# gps_and_sensor_20171211.net
KiCad netlist of a schematic drawn in EAGLE
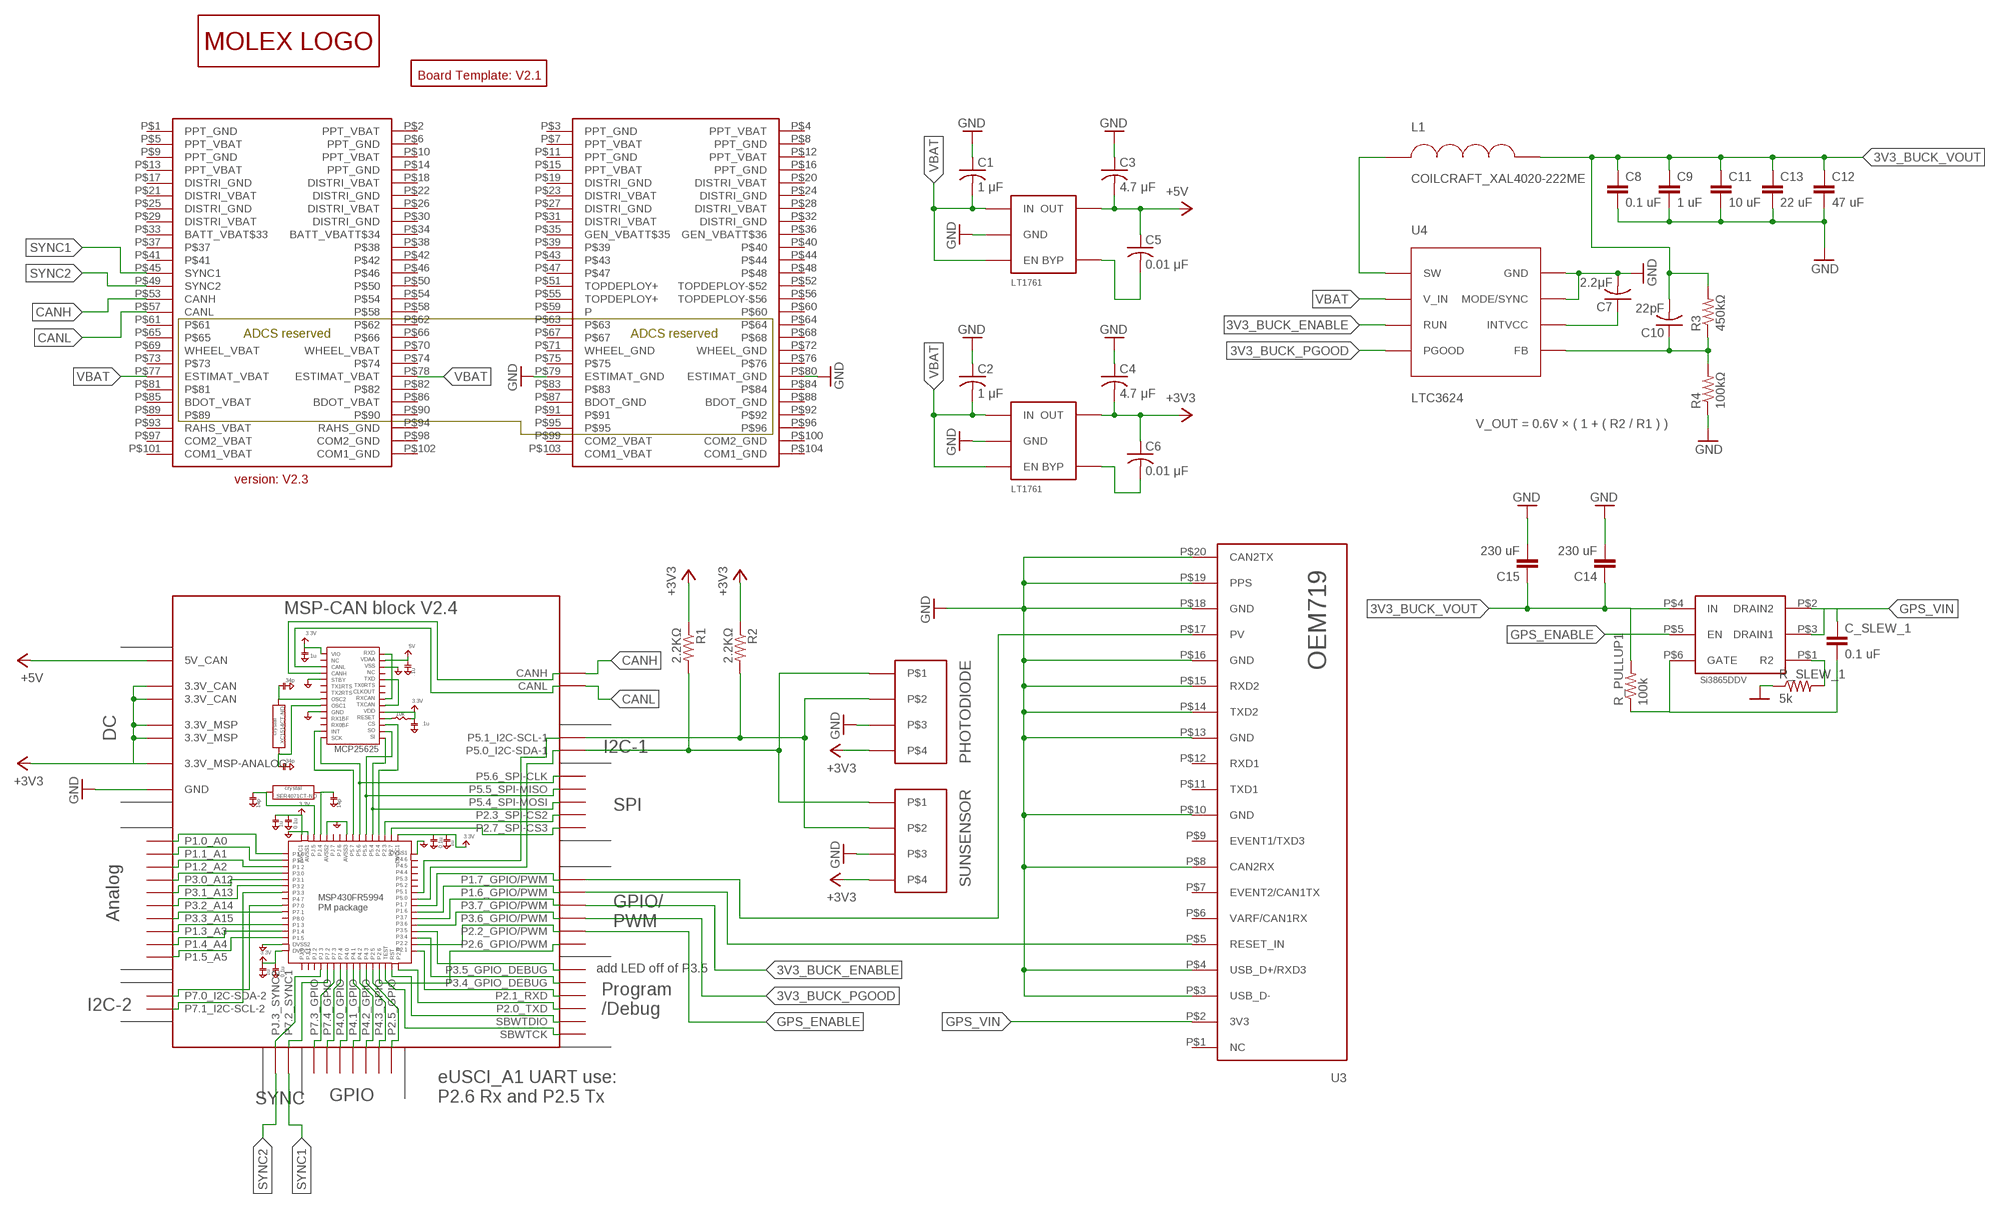
[diagram p0: schematic, sheet 1]

(export (version "E")
  (design (tool "Eeschema 10.0.6"))
  (components
    (comp (ref "B1")
      (value "BOARD_TEMPLATE1")
      (footprint "eagle-import:BOARD_TEMPLATE")
      (libsource (lib "eagle-import") (part "BOARD_TEMPLATE1"))
    )
    (comp (ref "BLK1")
      (value "MSP-CAN_BLOCK")
      (footprint "eagle-import:MSP-CAN_BLOCK")
      (libsource (lib "eagle-import") (part "MSP-CAN_BLOCK"))
    )
    (comp (ref "C1")
      (value "1 μF")
      (footprint "eagle-import:C0805")
      (libsource (lib "eagle-import") (part "C-USC0805"))
    )
    (comp (ref "C2")
      (value "1 μF")
      (footprint "eagle-import:C0805")
      (libsource (lib "eagle-import") (part "C-USC0805"))
    )
    (comp (ref "C3")
      (value "4.7 μF")
      (footprint "eagle-import:C0805")
      (libsource (lib "eagle-import") (part "C-USC0805"))
    )
    (comp (ref "C4")
      (value "4.7 μF")
      (footprint "eagle-import:C0805")
      (libsource (lib "eagle-import") (part "C-USC0805"))
    )
    (comp (ref "C5")
      (value "0.01 μF")
      (footprint "eagle-import:C0805")
      (libsource (lib "eagle-import") (part "C-USC0805"))
    )
    (comp (ref "C6")
      (value "0.01 μF")
      (footprint "eagle-import:C0805")
      (libsource (lib "eagle-import") (part "C-USC0805"))
    )
    (comp (ref "C7")
      (value "2.2μF")
      (footprint "eagle-import:C0805")
      (libsource (lib "eagle-import") (part "C-USC0805"))
    )
    (comp (ref "C8")
      (value "0.1 uF")
      (footprint "eagle-import:0805")
      (libsource (lib "eagle-import") (part "CAPACITOR0805"))
    )
    (comp (ref "C9")
      (value "1 uF")
      (footprint "eagle-import:0805")
      (libsource (lib "eagle-import") (part "CAPACITOR0805"))
    )
    (comp (ref "C10")
      (value "22pF")
      (footprint "eagle-import:C0805")
      (libsource (lib "eagle-import") (part "C-USC0805"))
    )
    (comp (ref "C11")
      (value "10 uF")
      (footprint "eagle-import:0805")
      (libsource (lib "eagle-import") (part "CAPACITOR0805"))
    )
    (comp (ref "C12")
      (value "47 uF")
      (footprint "eagle-import:1206")
      (libsource (lib "eagle-import") (part "CAPACITOR1206"))
    )
    (comp (ref "C13")
      (value "22 uF")
      (footprint "eagle-import:1206")
      (libsource (lib "eagle-import") (part "CAPACITOR1206"))
    )
    (comp (ref "C14")
      (value "230 uF")
      (footprint "eagle-import:PANASONIC_SVPG")
      (libsource (lib "eagle-import") (part "CAPACITORPANASONIC_16SVPG270M"))
    )
    (comp (ref "C15")
      (value "230 uF")
      (footprint "eagle-import:PANASONIC_SVPG")
      (libsource (lib "eagle-import") (part "CAPACITORPANASONIC_16SVPG270M"))
    )
    (comp (ref "CONN1")
      (value "PC104_CONNECTOR")
      (footprint "eagle-import:PC104_CONNECTOR")
      (libsource (lib "eagle-import") (part "PC104_CONNECTOR"))
    )
    (comp (ref "C_SLEW_1")
      (value "0.1 uF")
      (footprint "eagle-import:0805")
      (libsource (lib "eagle-import") (part "CAPACITOR0805"))
    )
    (comp (ref "L1")
      (value "COILCRAFT_XAL4020-222ME")
      (footprint "eagle-import:COILCRAFT_XAL4020")
      (libsource (lib "eagle-import") (part "COILCRAFT_XAL4020-222ME"))
    )
    (comp (ref "PHOTODIODE")
      (value "PICOLOCK_4")
      (footprint "eagle-import:PICOLOCK_4")
      (libsource (lib "eagle-import") (part "PICOLOCK_4"))
    )
    (comp (ref "R1")
      (value "2.2KΩ")
      (footprint "eagle-import:R0805")
      (libsource (lib "eagle-import") (part "R-US_R0805"))
    )
    (comp (ref "R2")
      (value "2.2KΩ")
      (footprint "eagle-import:R0805")
      (libsource (lib "eagle-import") (part "R-US_R0805"))
    )
    (comp (ref "R3")
      (value "450kΩ")
      (footprint "eagle-import:R0805")
      (libsource (lib "eagle-import") (part "R-US_R0805"))
    )
    (comp (ref "R4")
      (value "100kΩ")
      (footprint "eagle-import:R0805")
      (libsource (lib "eagle-import") (part "R-US_R0805"))
    )
    (comp (ref "R_PULLUP1")
      (value "100k")
      (footprint "eagle-import:0805")
      (libsource (lib "eagle-import") (part "RESISTOR0805"))
    )
    (comp (ref "R_SLEW_1")
      (value "5k")
      (footprint "eagle-import:0805")
      (libsource (lib "eagle-import") (part "RESISTOR0805"))
    )
    (comp (ref "SUNSENSOR")
      (value "PICOLOCK_4")
      (footprint "eagle-import:PICOLOCK_4")
      (libsource (lib "eagle-import") (part "PICOLOCK_4"))
    )
    (comp (ref "U$1")
      (value "LOGO_MOLEX")
      (footprint "eagle-import:LOGO_MOLEX")
      (libsource (lib "eagle-import") (part "LOGO_MOLEX"))
    )
    (comp (ref "U$3")
      (value "SI3865DDV")
      (footprint "eagle-import:TSOP-6")
      (libsource (lib "eagle-import") (part "SI3865DDV"))
    )
    (comp (ref "U1")
      (value "LINEAR_LDO_LT1761-X")
      (footprint "eagle-import:SOT-23-5")
      (libsource (lib "eagle-import") (part "LINEAR_LDO_LT1761-X"))
    )
    (comp (ref "U2")
      (value "LINEAR_LDO_LT1761-X")
      (footprint "eagle-import:SOT-23-5")
      (libsource (lib "eagle-import") (part "LINEAR_LDO_LT1761-X"))
    )
    (comp (ref "U3")
      (value "OEM719")
      (footprint "eagle-import:OEM719")
      (libsource (lib "eagle-import") (part "OEM719"))
    )
    (comp (ref "U4")
      (value "LTC3624")
      (footprint "eagle-import:LTC3624")
      (libsource (lib "eagle-import") (part "LTC3624"))
    )
  )
  (nets
    (net (code "1") (name "+3V3") (class "Default")
      (node (ref "BLK1") (pin "3.3V@CAN1") (pinfunction "3.3V_CAN_3.3V@CAN1") (pintype "bidirectional"))
      (node (ref "BLK1") (pin "3.3V@CAN2") (pinfunction "3.3V_CAN_3.3V@CAN2") (pintype "bidirectional"))
      (node (ref "BLK1") (pin "3.3V@MSP1") (pinfunction "3.3V_MSP_3.3V@MSP1") (pintype "bidirectional"))
      (node (ref "BLK1") (pin "3.3V@MSP2") (pinfunction "3.3V_MSP_3.3V@MSP2") (pintype "bidirectional"))
      (node (ref "BLK1") (pin "3.3V_ANALOG@MSP2") (pinfunction "3.3V_MSP-ANALOG_3.3V_ANALOG@MSP2") (pintype "bidirectional"))
      (node (ref "C4") (pin "2") (pinfunction "2_2") (pintype "passive"))
      (node (ref "C6") (pin "1") (pinfunction "1_1") (pintype "passive"))
      (node (ref "PHOTODIODE") (pin "P$4") (pinfunction "P$4_P$4") (pintype "bidirectional"))
      (node (ref "R1") (pin "1") (pinfunction "1_1") (pintype "passive"))
      (node (ref "R2") (pin "1") (pinfunction "1_1") (pintype "passive"))
      (node (ref "SUNSENSOR") (pin "P$4") (pinfunction "P$4_P$4") (pintype "bidirectional"))
      (node (ref "U2") (pin "P$5") (pinfunction "OUT_P$5") (pintype "bidirectional"))
    )
    (net (code "2") (name "+5V") (class "Default")
      (node (ref "BLK1") (pin "5V") (pinfunction "5V_CAN_5V") (pintype "bidirectional"))
      (node (ref "C3") (pin "2") (pinfunction "2_2") (pintype "passive"))
      (node (ref "C5") (pin "1") (pinfunction "1_1") (pintype "passive"))
      (node (ref "U1") (pin "P$5") (pinfunction "OUT_P$5") (pintype "bidirectional"))
    )
    (net (code "3") (name "3V3_BUCK_ENABLE") (class "Default")
      (node (ref "BLK1") (pin "P3.7_GPIO/PWM") (pinfunction "P3.7_GPIO/PWM_P3.7_GPIO/PWM") (pintype "bidirectional"))
      (node (ref "U4") (pin "RUN") (pinfunction "RUN_RUN") (pintype "bidirectional"))
    )
    (net (code "4") (name "3V3_BUCK_PGOOD") (class "Default")
      (node (ref "BLK1") (pin "P3.6_GPIO/PWM") (pinfunction "P3.6_GPIO/PWM_P3.6_GPIO/PWM") (pintype "bidirectional"))
      (node (ref "U4") (pin "PGOOD") (pinfunction "PGOOD_PGOOD") (pintype "bidirectional"))
    )
    (net (code "5") (name "3V3_BUCK_VOUT") (class "Default")
      (node (ref "C10") (pin "2") (pinfunction "2_2") (pintype "passive"))
      (node (ref "C11") (pin "1") (pinfunction "1_1") (pintype "passive"))
      (node (ref "C12") (pin "1") (pinfunction "1_1") (pintype "passive"))
      (node (ref "C13") (pin "1") (pinfunction "1_1") (pintype "passive"))
      (node (ref "C14") (pin "POS") (pinfunction "1_POS") (pintype "passive"))
      (node (ref "C15") (pin "POS") (pinfunction "1_POS") (pintype "passive"))
      (node (ref "C8") (pin "1") (pinfunction "1_1") (pintype "passive"))
      (node (ref "C9") (pin "1") (pinfunction "1_1") (pintype "passive"))
      (node (ref "L1") (pin "P$2") (pinfunction "P$2_P$2") (pintype "bidirectional"))
      (node (ref "R3") (pin "2") (pinfunction "2_2") (pintype "passive"))
      (node (ref "R_PULLUP1") (pin "2") (pinfunction "2_2") (pintype "passive"))
      (node (ref "U$3") (pin "P$4") (pinfunction "IN_P$4") (pintype "bidirectional"))
    )
    (net (code "6") (name "CANH") (class "Default")
      (node (ref "BLK1") (pin "CANH") (pinfunction "CANH_CANH") (pintype "bidirectional"))
      (node (ref "CONN1") (pin "P$53") (pinfunction "CANH_P$53") (pintype "bidirectional"))
    )
    (net (code "7") (name "CANL") (class "Default")
      (node (ref "BLK1") (pin "CANL") (pinfunction "CANL_CANL") (pintype "bidirectional"))
      (node (ref "CONN1") (pin "P$57") (pinfunction "CANL_P$57") (pintype "bidirectional"))
    )
    (net (code "8") (name "DGND") (class "Default")
      (node (ref "BLK1") (pin "GND@1") (pinfunction "GND_GND@1") (pintype "bidirectional"))
      (node (ref "BLK1") (pin "GND@10") (pinfunction "GND_GND@10") (pintype "bidirectional"))
      (node (ref "BLK1") (pin "GND@11") (pinfunction "GND_GND@11") (pintype "bidirectional"))
      (node (ref "BLK1") (pin "GND@12") (pinfunction "GND_GND@12") (pintype "bidirectional"))
      (node (ref "BLK1") (pin "GND@13") (pinfunction "GND_GND@13") (pintype "bidirectional"))
      (node (ref "BLK1") (pin "GND@14") (pinfunction "GND_GND@14") (pintype "bidirectional"))
      (node (ref "BLK1") (pin "GND@15") (pinfunction "GND_GND@15") (pintype "bidirectional"))
      (node (ref "BLK1") (pin "GND@16") (pinfunction "GND_GND@16") (pintype "bidirectional"))
      (node (ref "BLK1") (pin "GND@17") (pinfunction "GND_GND@17") (pintype "bidirectional"))
      (node (ref "BLK1") (pin "GND@2") (pinfunction "GND_GND@2") (pintype "bidirectional"))
      (node (ref "BLK1") (pin "GND@26") (pinfunction "GND_GND@26") (pintype "bidirectional"))
      (node (ref "BLK1") (pin "GND@3") (pinfunction "GND_GND@3") (pintype "bidirectional"))
      (node (ref "BLK1") (pin "GND@4") (pinfunction "GND_GND@4") (pintype "bidirectional"))
      (node (ref "BLK1") (pin "GND@5") (pinfunction "GND_GND@5") (pintype "bidirectional"))
      (node (ref "BLK1") (pin "GND@7") (pinfunction "GND_GND@7") (pintype "bidirectional"))
      (node (ref "BLK1") (pin "GND@8") (pinfunction "GND_GND@8") (pintype "bidirectional"))
      (node (ref "BLK1") (pin "GND@9") (pinfunction "GND_GND@9") (pintype "bidirectional"))
      (node (ref "C1") (pin "1") (pinfunction "1_1") (pintype "passive"))
      (node (ref "C11") (pin "2") (pinfunction "2_2") (pintype "passive"))
      (node (ref "C12") (pin "2") (pinfunction "2_2") (pintype "passive"))
      (node (ref "C13") (pin "2") (pinfunction "2_2") (pintype "passive"))
      (node (ref "C14") (pin "NEG") (pinfunction "2_NEG") (pintype "passive"))
      (node (ref "C15") (pin "NEG") (pinfunction "2_NEG") (pintype "passive"))
      (node (ref "C2") (pin "1") (pinfunction "1_1") (pintype "passive"))
      (node (ref "C3") (pin "1") (pinfunction "1_1") (pintype "passive"))
      (node (ref "C4") (pin "1") (pinfunction "1_1") (pintype "passive"))
      (node (ref "C7") (pin "2") (pinfunction "2_2") (pintype "passive"))
      (node (ref "C8") (pin "2") (pinfunction "2_2") (pintype "passive"))
      (node (ref "C9") (pin "2") (pinfunction "2_2") (pintype "passive"))
      (node (ref "CONN1") (pin "P$79") (pinfunction "ESTIMAT_GND_P$79") (pintype "bidirectional"))
      (node (ref "CONN1") (pin "P$80") (pinfunction "ESTIMAT_GND_P$80") (pintype "bidirectional"))
      (node (ref "PHOTODIODE") (pin "P$3") (pinfunction "P$3_P$3") (pintype "bidirectional"))
      (node (ref "R4") (pin "1") (pinfunction "1_1") (pintype "passive"))
      (node (ref "R_SLEW_1") (pin "1") (pinfunction "1_1") (pintype "passive"))
      (node (ref "SUNSENSOR") (pin "P$3") (pinfunction "P$3_P$3") (pintype "bidirectional"))
      (node (ref "U1") (pin "P$2") (pinfunction "GND_P$2") (pintype "bidirectional"))
      (node (ref "U2") (pin "P$2") (pinfunction "GND_P$2") (pintype "bidirectional"))
      (node (ref "U3") (pin "P$10") (pinfunction "GND_P$10") (pintype "bidirectional"))
      (node (ref "U3") (pin "P$13") (pinfunction "GND_P$13") (pintype "bidirectional"))
      (node (ref "U3") (pin "P$14") (pinfunction "TXD2_P$14") (pintype "bidirectional"))
      (node (ref "U3") (pin "P$15") (pinfunction "RXD2_P$15") (pintype "bidirectional"))
      (node (ref "U3") (pin "P$16") (pinfunction "GND_P$16") (pintype "bidirectional"))
      (node (ref "U3") (pin "P$18") (pinfunction "GND_P$18") (pintype "bidirectional"))
      (node (ref "U3") (pin "P$19") (pinfunction "PPS_P$19") (pintype "bidirectional"))
      (node (ref "U3") (pin "P$20") (pinfunction "CAN2TX_P$20") (pintype "bidirectional"))
      (node (ref "U3") (pin "P$3") (pinfunction "USB_D-_P$3") (pintype "bidirectional"))
      (node (ref "U3") (pin "P$4") (pinfunction "USB_D+/RXD3_P$4") (pintype "bidirectional"))
      (node (ref "U3") (pin "P$8") (pinfunction "CAN2RX_P$8") (pintype "bidirectional"))
      (node (ref "U4") (pin "GND@1") (pinfunction "GND_GND@1") (pintype "bidirectional"))
      (node (ref "U4") (pin "GND@PAD") (pinfunction "GND_GND@PAD") (pintype "bidirectional"))
      (node (ref "U4") (pin "MODE/SYNC") (pinfunction "MODE/SYNC_MODE/SYNC") (pintype "bidirectional"))
    )
    (net (code "9") (name "GPS_ENABLE") (class "Default")
      (node (ref "BLK1") (pin "P2.2_GPIO/PWM") (pinfunction "P2.2_GPIO/PWM_P2.2_GPIO/PWM") (pintype "bidirectional"))
      (node (ref "U$3") (pin "P$5") (pinfunction "EN_P$5") (pintype "bidirectional"))
    )
    (net (code "10") (name "GPS_VIN") (class "Default")
      (node (ref "C_SLEW_1") (pin "1") (pinfunction "1_1") (pintype "passive"))
      (node (ref "U$3") (pin "P$2") (pinfunction "DRAIN2_P$2") (pintype "bidirectional"))
      (node (ref "U$3") (pin "P$3") (pinfunction "DRAIN1_P$3") (pintype "bidirectional"))
      (node (ref "U3") (pin "P$2") (pinfunction "3V3_P$2") (pintype "bidirectional"))
    )
    (net (code "11") (name "Net-(BLK1-PadP5.0_I2C-SDA-1)") (class "Default")
      (node (ref "BLK1") (pin "P5.0_I2C-SDA-1") (pinfunction "P5.0_I2C-SDA-1_P5.0_I2C-SDA-1") (pintype "bidirectional"))
      (node (ref "PHOTODIODE") (pin "P$1") (pinfunction "P$1_P$1") (pintype "bidirectional"))
      (node (ref "R1") (pin "2") (pinfunction "2_2") (pintype "passive"))
      (node (ref "SUNSENSOR") (pin "P$1") (pinfunction "P$1_P$1") (pintype "bidirectional"))
    )
    (net (code "12") (name "Net-(BLK1-PadP5.1_I2C-SCL-1)") (class "Default")
      (node (ref "BLK1") (pin "P5.1_I2C-SCL-1") (pinfunction "P5.1_I2C-SCL-1_P5.1_I2C-SCL-1") (pintype "bidirectional"))
      (node (ref "PHOTODIODE") (pin "P$2") (pinfunction "P$2_P$2") (pintype "bidirectional"))
      (node (ref "R2") (pin "2") (pinfunction "2_2") (pintype "passive"))
      (node (ref "SUNSENSOR") (pin "P$2") (pinfunction "P$2_P$2") (pintype "bidirectional"))
    )
    (net (code "13") (name "Net-(C7-Pad1)") (class "Default")
      (node (ref "C7") (pin "1") (pinfunction "1_1") (pintype "passive"))
      (node (ref "U4") (pin "INTVCC") (pinfunction "INTVCC_INTVCC") (pintype "bidirectional"))
    )
    (net (code "14") (name "Net-(C10-Pad1)") (class "Default")
      (node (ref "C10") (pin "1") (pinfunction "1_1") (pintype "passive"))
      (node (ref "R3") (pin "1") (pinfunction "1_1") (pintype "passive"))
      (node (ref "R4") (pin "2") (pinfunction "2_2") (pintype "passive"))
      (node (ref "U4") (pin "FB") (pinfunction "FB_FB") (pintype "bidirectional"))
    )
    (net (code "15") (name "Net-(L1-PadP$1)") (class "Default")
      (node (ref "L1") (pin "P$1") (pinfunction "P$1_P$1") (pintype "bidirectional"))
      (node (ref "U4") (pin "SW") (pinfunction "SW_SW") (pintype "bidirectional"))
    )
    (net (code "16") (name "Net-(U$3-GATE)") (class "Default")
      (node (ref "C_SLEW_1") (pin "2") (pinfunction "2_2") (pintype "passive"))
      (node (ref "R_PULLUP1") (pin "1") (pinfunction "1_1") (pintype "passive"))
      (node (ref "U$3") (pin "P$6") (pinfunction "GATE_P$6") (pintype "bidirectional"))
    )
    (net (code "17") (name "Net-(U$3-R2)") (class "Default")
      (node (ref "R_SLEW_1") (pin "2") (pinfunction "2_2") (pintype "passive"))
      (node (ref "U$3") (pin "P$1") (pinfunction "R2_P$1") (pintype "bidirectional"))
    )
    (net (code "18") (name "Net-(U1-BYP)") (class "Default")
      (node (ref "C5") (pin "2") (pinfunction "2_2") (pintype "passive"))
      (node (ref "U1") (pin "P$4") (pinfunction "BYP_P$4") (pintype "bidirectional"))
    )
    (net (code "19") (name "Net-(U2-BYP)") (class "Default")
      (node (ref "C6") (pin "2") (pinfunction "2_2") (pintype "passive"))
      (node (ref "U2") (pin "P$4") (pinfunction "BYP_P$4") (pintype "bidirectional"))
    )
    (net (code "20") (name "Net-(U3-PV)") (class "Default")
      (node (ref "BLK1") (pin "P1.7_GPIO/PWM") (pinfunction "P1.7_GPIO/PWM_P1.7_GPIO/PWM") (pintype "bidirectional"))
      (node (ref "U3") (pin "P$17") (pinfunction "PV_P$17") (pintype "bidirectional"))
    )
    (net (code "21") (name "Net-(U3-RESET_IN)") (class "Default")
      (node (ref "BLK1") (pin "P1.6_GPIO/PWM") (pinfunction "P1.6_GPIO/PWM_P1.6_GPIO/PWM") (pintype "bidirectional"))
      (node (ref "U3") (pin "P$5") (pinfunction "RESET_IN_P$5") (pintype "bidirectional"))
    )
    (net (code "22") (name "SYNC1") (class "Default")
      (node (ref "BLK1") (pin "P7.2_SYNC1") (pinfunction "P7.2_SYNC1_P7.2_SYNC1") (pintype "bidirectional"))
      (node (ref "CONN1") (pin "P$45") (pinfunction "SYNC1_P$45") (pintype "bidirectional"))
    )
    (net (code "23") (name "SYNC2") (class "Default")
      (node (ref "BLK1") (pin "PJ.3_SYNC2") (pinfunction "PJ.3_SYNC2_PJ.3_SYNC2") (pintype "bidirectional"))
      (node (ref "CONN1") (pin "P$49") (pinfunction "SYNC2_P$49") (pintype "bidirectional"))
    )
    (net (code "24") (name "VBAT") (class "Default")
      (node (ref "C1") (pin "2") (pinfunction "2_2") (pintype "passive"))
      (node (ref "C2") (pin "2") (pinfunction "2_2") (pintype "passive"))
      (node (ref "CONN1") (pin "P$77") (pinfunction "ESTIMAT_VBAT_P$77") (pintype "bidirectional"))
      (node (ref "CONN1") (pin "P$78") (pinfunction "ESTIMAT_VBAT_P$78") (pintype "bidirectional"))
      (node (ref "U1") (pin "P$1") (pinfunction "IN_P$1") (pintype "bidirectional"))
      (node (ref "U1") (pin "P$3") (pinfunction "EN_P$3") (pintype "bidirectional"))
      (node (ref "U2") (pin "P$1") (pinfunction "IN_P$1") (pintype "bidirectional"))
      (node (ref "U2") (pin "P$3") (pinfunction "EN_P$3") (pintype "bidirectional"))
      (node (ref "U4") (pin "V_IN") (pinfunction "V_IN_V_IN") (pintype "bidirectional"))
    )
    (net (code "25") (name "unconnected-(BLK1-P2.3_SPI-CS2-PadP2.4_SPI-CS2)") (class "Default")
      (node (ref "BLK1") (pin "P2.4_SPI-CS2") (pinfunction "P2.3_SPI-CS2_P2.4_SPI-CS2") (pintype "bidirectional"))
    )
    (net (code "26") (name "unconnected-(BLK1-PadP1.0_A0)") (class "Default")
      (node (ref "BLK1") (pin "P1.0_A0") (pinfunction "P1.0_A0_P1.0_A0") (pintype "bidirectional"))
    )
    (net (code "27") (name "unconnected-(BLK1-PadP1.1_A1)") (class "Default")
      (node (ref "BLK1") (pin "P1.1_A1") (pinfunction "P1.1_A1_P1.1_A1") (pintype "bidirectional"))
    )
    (net (code "28") (name "unconnected-(BLK1-PadP1.2_A2)") (class "Default")
      (node (ref "BLK1") (pin "P1.2_A2") (pinfunction "P1.2_A2_P1.2_A2") (pintype "bidirectional"))
    )
    (net (code "29") (name "unconnected-(BLK1-PadP1.3_A3)") (class "Default")
      (node (ref "BLK1") (pin "P1.3_A3") (pinfunction "P1.3_A3_P1.3_A3") (pintype "bidirectional"))
    )
    (net (code "30") (name "unconnected-(BLK1-PadP1.4_A4)") (class "Default")
      (node (ref "BLK1") (pin "P1.4_A4") (pinfunction "P1.4_A4_P1.4_A4") (pintype "bidirectional"))
    )
    (net (code "31") (name "unconnected-(BLK1-PadP1.5_A5)") (class "Default")
      (node (ref "BLK1") (pin "P1.5_A5") (pinfunction "P1.5_A5_P1.5_A5") (pintype "bidirectional"))
    )
    (net (code "32") (name "unconnected-(BLK1-PadP2.0_TXD)") (class "Default")
      (node (ref "BLK1") (pin "P2.0_TXD") (pinfunction "P2.0_TXD_P2.0_TXD") (pintype "bidirectional"))
    )
    (net (code "33") (name "unconnected-(BLK1-PadP2.1_RXD)") (class "Default")
      (node (ref "BLK1") (pin "P2.1_RXD") (pinfunction "P2.1_RXD_P2.1_RXD") (pintype "bidirectional"))
    )
    (net (code "34") (name "unconnected-(BLK1-PadP2.5_GPIO)") (class "Default")
      (node (ref "BLK1") (pin "P2.5_GPIO") (pinfunction "P2.5_GPIO_P2.5_GPIO") (pintype "bidirectional"))
    )
    (net (code "35") (name "unconnected-(BLK1-PadP2.6_GPIO{slash}PWM)") (class "Default")
      (node (ref "BLK1") (pin "P2.6_GPIO/PWM") (pinfunction "P2.6_GPIO/PWM_P2.6_GPIO/PWM") (pintype "bidirectional"))
    )
    (net (code "36") (name "unconnected-(BLK1-PadP2.7_SPI-CS3)") (class "Default")
      (node (ref "BLK1") (pin "P2.7_SPI-CS3") (pinfunction "P2.7_SPI-CS3_P2.7_SPI-CS3") (pintype "bidirectional"))
    )
    (net (code "37") (name "unconnected-(BLK1-PadP3.0_A12)") (class "Default")
      (node (ref "BLK1") (pin "P3.0_A12") (pinfunction "P3.0_A12_P3.0_A12") (pintype "bidirectional"))
    )
    (net (code "38") (name "unconnected-(BLK1-PadP3.1_A13)") (class "Default")
      (node (ref "BLK1") (pin "P3.1_A13") (pinfunction "P3.1_A13_P3.1_A13") (pintype "bidirectional"))
    )
    (net (code "39") (name "unconnected-(BLK1-PadP3.2_A14)") (class "Default")
      (node (ref "BLK1") (pin "P3.2_A14") (pinfunction "P3.2_A14_P3.2_A14") (pintype "bidirectional"))
    )
    (net (code "40") (name "unconnected-(BLK1-PadP3.3_A15)") (class "Default")
      (node (ref "BLK1") (pin "P3.3_A15") (pinfunction "P3.3_A15_P3.3_A15") (pintype "bidirectional"))
    )
    (net (code "41") (name "unconnected-(BLK1-PadP3.4_GPIO_DEBUG)") (class "Default")
      (node (ref "BLK1") (pin "P3.4_GPIO_DEBUG") (pinfunction "P3.4_GPIO_DEBUG_P3.4_GPIO_DEBUG") (pintype "bidirectional"))
    )
    (net (code "42") (name "unconnected-(BLK1-PadP3.5_GPIO_DEBUG)") (class "Default")
      (node (ref "BLK1") (pin "P3.5_GPIO_DEBUG") (pinfunction "P3.5_GPIO_DEBUG_P3.5_GPIO_DEBUG") (pintype "bidirectional"))
    )
    (net (code "43") (name "unconnected-(BLK1-PadP4.0_GPIO)") (class "Default")
      (node (ref "BLK1") (pin "P4.0_GPIO") (pinfunction "P4.0_GPIO_P4.0_GPIO") (pintype "bidirectional"))
    )
    (net (code "44") (name "unconnected-(BLK1-PadP4.1_GPIO)") (class "Default")
      (node (ref "BLK1") (pin "P4.1_GPIO") (pinfunction "P4.1_GPIO_P4.1_GPIO") (pintype "bidirectional"))
    )
    (net (code "45") (name "unconnected-(BLK1-PadP4.2_GPIO)") (class "Default")
      (node (ref "BLK1") (pin "P4.2_GPIO") (pinfunction "P4.2_GPIO_P4.2_GPIO") (pintype "bidirectional"))
    )
    (net (code "46") (name "unconnected-(BLK1-PadP4.3_GPIO)") (class "Default")
      (node (ref "BLK1") (pin "P4.3_GPIO") (pinfunction "P4.3_GPIO_P4.3_GPIO") (pintype "bidirectional"))
    )
    (net (code "47") (name "unconnected-(BLK1-PadP5.4_SPI-MOSI)") (class "Default")
      (node (ref "BLK1") (pin "P5.4_SPI-MOSI") (pinfunction "P5.4_SPI-MOSI_P5.4_SPI-MOSI") (pintype "bidirectional"))
    )
    (net (code "48") (name "unconnected-(BLK1-PadP5.5_SPI-MISO)") (class "Default")
      (node (ref "BLK1") (pin "P5.5_SPI-MISO") (pinfunction "P5.5_SPI-MISO_P5.5_SPI-MISO") (pintype "bidirectional"))
    )
    (net (code "49") (name "unconnected-(BLK1-PadP5.6_SPI-CLK)") (class "Default")
      (node (ref "BLK1") (pin "P5.6_SPI-CLK") (pinfunction "P5.6_SPI-CLK_P5.6_SPI-CLK") (pintype "bidirectional"))
    )
    (net (code "50") (name "unconnected-(BLK1-PadP7.0_I2C-SDA-2)") (class "Default")
      (node (ref "BLK1") (pin "P7.0_I2C-SDA-2") (pinfunction "P7.0_I2C-SDA-2_P7.0_I2C-SDA-2") (pintype "bidirectional"))
    )
    (net (code "51") (name "unconnected-(BLK1-PadP7.1_I2C-SCL-2)") (class "Default")
      (node (ref "BLK1") (pin "P7.1_I2C-SCL-2") (pinfunction "P7.1_I2C-SCL-2_P7.1_I2C-SCL-2") (pintype "bidirectional"))
    )
    (net (code "52") (name "unconnected-(BLK1-PadP7.3_GPIO)") (class "Default")
      (node (ref "BLK1") (pin "P7.3_GPIO") (pinfunction "P7.3_GPIO_P7.3_GPIO") (pintype "bidirectional"))
    )
    (net (code "53") (name "unconnected-(BLK1-PadP7.4_GPIO)") (class "Default")
      (node (ref "BLK1") (pin "P7.4_GPIO") (pinfunction "P7.4_GPIO_P7.4_GPIO") (pintype "bidirectional"))
    )
    (net (code "54") (name "unconnected-(BLK1-PadSBWTCK)") (class "Default")
      (node (ref "BLK1") (pin "SBWTCK") (pinfunction "SBWTCK_SBWTCK") (pintype "bidirectional"))
    )
    (net (code "55") (name "unconnected-(BLK1-PadSBWTDIO)") (class "Default")
      (node (ref "BLK1") (pin "SBWTDIO") (pinfunction "SBWTDIO_SBWTDIO") (pintype "bidirectional"))
    )
    (net (code "56") (name "unconnected-(CONN1-BATT_VBAT$33-PadP$33)") (class "Default")
      (node (ref "CONN1") (pin "P$33") (pinfunction "BATT_VBAT$33_P$33") (pintype "bidirectional"))
    )
    (net (code "57") (name "unconnected-(CONN1-BATT_VBATT$34-PadP$34)") (class "Default")
      (node (ref "CONN1") (pin "P$34") (pinfunction "BATT_VBATT$34_P$34") (pintype "bidirectional"))
    )
    (net (code "58") (name "unconnected-(CONN1-BDOT_GND-PadP$87)") (class "Default")
      (node (ref "CONN1") (pin "P$87") (pinfunction "BDOT_GND_P$87") (pintype "bidirectional"))
    )
    (net (code "59") (name "unconnected-(CONN1-BDOT_GND-PadP$88)") (class "Default")
      (node (ref "CONN1") (pin "P$88") (pinfunction "BDOT_GND_P$88") (pintype "bidirectional"))
    )
    (net (code "60") (name "unconnected-(CONN1-BDOT_VBAT-PadP$85)") (class "Default")
      (node (ref "CONN1") (pin "P$85") (pinfunction "BDOT_VBAT_P$85") (pintype "bidirectional"))
    )
    (net (code "61") (name "unconnected-(CONN1-BDOT_VBAT-PadP$86)") (class "Default")
      (node (ref "CONN1") (pin "P$86") (pinfunction "BDOT_VBAT_P$86") (pintype "bidirectional"))
    )
    (net (code "62") (name "unconnected-(CONN1-COM1_GND-PadP$102)") (class "Default")
      (node (ref "CONN1") (pin "P$102") (pinfunction "COM1_GND_P$102") (pintype "bidirectional"))
    )
    (net (code "63") (name "unconnected-(CONN1-COM1_GND-PadP$104)") (class "Default")
      (node (ref "CONN1") (pin "P$104") (pinfunction "COM1_GND_P$104") (pintype "bidirectional"))
    )
    (net (code "64") (name "unconnected-(CONN1-COM1_VBAT-PadP$101)") (class "Default")
      (node (ref "CONN1") (pin "P$101") (pinfunction "COM1_VBAT_P$101") (pintype "bidirectional"))
    )
    (net (code "65") (name "unconnected-(CONN1-COM1_VBAT-PadP$103)") (class "Default")
      (node (ref "CONN1") (pin "P$103") (pinfunction "COM1_VBAT_P$103") (pintype "bidirectional"))
    )
    (net (code "66") (name "unconnected-(CONN1-COM2_GND-PadP$98)") (class "Default")
      (node (ref "CONN1") (pin "P$98") (pinfunction "COM2_GND_P$98") (pintype "bidirectional"))
    )
    (net (code "67") (name "unconnected-(CONN1-COM2_GND-PadP$100)") (class "Default")
      (node (ref "CONN1") (pin "P$100") (pinfunction "COM2_GND_P$100") (pintype "bidirectional"))
    )
    (net (code "68") (name "unconnected-(CONN1-COM2_VBAT-PadP$97)") (class "Default")
      (node (ref "CONN1") (pin "P$97") (pinfunction "COM2_VBAT_P$97") (pintype "bidirectional"))
    )
    (net (code "69") (name "unconnected-(CONN1-COM2_VBAT-PadP$99)") (class "Default")
      (node (ref "CONN1") (pin "P$99") (pinfunction "COM2_VBAT_P$99") (pintype "bidirectional"))
    )
    (net (code "70") (name "unconnected-(CONN1-DISTRI_GND-PadP$17)") (class "Default")
      (node (ref "CONN1") (pin "P$17") (pinfunction "DISTRI_GND_P$17") (pintype "bidirectional"))
    )
    (net (code "71") (name "unconnected-(CONN1-DISTRI_GND-PadP$19)") (class "Default")
      (node (ref "CONN1") (pin "P$19") (pinfunction "DISTRI_GND_P$19") (pintype "bidirectional"))
    )
    (net (code "72") (name "unconnected-(CONN1-DISTRI_GND-PadP$22)") (class "Default")
      (node (ref "CONN1") (pin "P$22") (pinfunction "DISTRI_GND_P$22") (pintype "bidirectional"))
    )
    (net (code "73") (name "unconnected-(CONN1-DISTRI_GND-PadP$24)") (class "Default")
      (node (ref "CONN1") (pin "P$24") (pinfunction "DISTRI_GND_P$24") (pintype "bidirectional"))
    )
    (net (code "74") (name "unconnected-(CONN1-DISTRI_GND-PadP$25)") (class "Default")
      (node (ref "CONN1") (pin "P$25") (pinfunction "DISTRI_GND_P$25") (pintype "bidirectional"))
    )
    (net (code "75") (name "unconnected-(CONN1-DISTRI_GND-PadP$27)") (class "Default")
      (node (ref "CONN1") (pin "P$27") (pinfunction "DISTRI_GND_P$27") (pintype "bidirectional"))
    )
    (net (code "76") (name "unconnected-(CONN1-DISTRI_GND-PadP$30)") (class "Default")
      (node (ref "CONN1") (pin "P$30") (pinfunction "DISTRI_GND_P$30") (pintype "bidirectional"))
    )
    (net (code "77") (name "unconnected-(CONN1-DISTRI_GND-PadP$32)") (class "Default")
      (node (ref "CONN1") (pin "P$32") (pinfunction "DISTRI_GND_P$32") (pintype "bidirectional"))
    )
    (net (code "78") (name "unconnected-(CONN1-DISTRI_VBAT-PadP$18)") (class "Default")
      (node (ref "CONN1") (pin "P$18") (pinfunction "DISTRI_VBAT_P$18") (pintype "bidirectional"))
    )
    (net (code "79") (name "unconnected-(CONN1-DISTRI_VBAT-PadP$20)") (class "Default")
      (node (ref "CONN1") (pin "P$20") (pinfunction "DISTRI_VBAT_P$20") (pintype "bidirectional"))
    )
    (net (code "80") (name "unconnected-(CONN1-DISTRI_VBAT-PadP$21)") (class "Default")
      (node (ref "CONN1") (pin "P$21") (pinfunction "DISTRI_VBAT_P$21") (pintype "bidirectional"))
    )
    (net (code "81") (name "unconnected-(CONN1-DISTRI_VBAT-PadP$23)") (class "Default")
      (node (ref "CONN1") (pin "P$23") (pinfunction "DISTRI_VBAT_P$23") (pintype "bidirectional"))
    )
    (net (code "82") (name "unconnected-(CONN1-DISTRI_VBAT-PadP$26)") (class "Default")
      (node (ref "CONN1") (pin "P$26") (pinfunction "DISTRI_VBAT_P$26") (pintype "bidirectional"))
    )
    (net (code "83") (name "unconnected-(CONN1-DISTRI_VBAT-PadP$28)") (class "Default")
      (node (ref "CONN1") (pin "P$28") (pinfunction "DISTRI_VBAT_P$28") (pintype "bidirectional"))
    )
    (net (code "84") (name "unconnected-(CONN1-DISTRI_VBAT-PadP$29)") (class "Default")
      (node (ref "CONN1") (pin "P$29") (pinfunction "DISTRI_VBAT_P$29") (pintype "bidirectional"))
    )
    (net (code "85") (name "unconnected-(CONN1-DISTRI_VBAT-PadP$31)") (class "Default")
      (node (ref "CONN1") (pin "P$31") (pinfunction "DISTRI_VBAT_P$31") (pintype "bidirectional"))
    )
    (net (code "86") (name "unconnected-(CONN1-GEN_VBATT$35-PadP$35)") (class "Default")
      (node (ref "CONN1") (pin "P$35") (pinfunction "GEN_VBATT$35_P$35") (pintype "bidirectional"))
    )
    (net (code "87") (name "unconnected-(CONN1-GEN_VBATT$36-PadP$36)") (class "Default")
      (node (ref "CONN1") (pin "P$36") (pinfunction "GEN_VBATT$36_P$36") (pintype "bidirectional"))
    )
    (net (code "88") (name "unconnected-(CONN1-P-PadP$59)") (class "Default")
      (node (ref "CONN1") (pin "P$59") (pinfunction "P_P$59") (pintype "bidirectional"))
    )
    (net (code "89") (name "unconnected-(CONN1-PPT_GND-PadP$1)") (class "Default")
      (node (ref "CONN1") (pin "P$1") (pinfunction "PPT_GND_P$1") (pintype "bidirectional"))
    )
    (net (code "90") (name "unconnected-(CONN1-PPT_GND-PadP$3)") (class "Default")
      (node (ref "CONN1") (pin "P$3") (pinfunction "PPT_GND_P$3") (pintype "bidirectional"))
    )
    (net (code "91") (name "unconnected-(CONN1-PPT_GND-PadP$6)") (class "Default")
      (node (ref "CONN1") (pin "P$6") (pinfunction "PPT_GND_P$6") (pintype "bidirectional"))
    )
    (net (code "92") (name "unconnected-(CONN1-PPT_GND-PadP$8)") (class "Default")
      (node (ref "CONN1") (pin "P$8") (pinfunction "PPT_GND_P$8") (pintype "bidirectional"))
    )
    (net (code "93") (name "unconnected-(CONN1-PPT_GND-PadP$9)") (class "Default")
      (node (ref "CONN1") (pin "P$9") (pinfunction "PPT_GND_P$9") (pintype "bidirectional"))
    )
    (net (code "94") (name "unconnected-(CONN1-PPT_GND-PadP$11)") (class "Default")
      (node (ref "CONN1") (pin "P$11") (pinfunction "PPT_GND_P$11") (pintype "bidirectional"))
    )
    (net (code "95") (name "unconnected-(CONN1-PPT_GND-PadP$14)") (class "Default")
      (node (ref "CONN1") (pin "P$14") (pinfunction "PPT_GND_P$14") (pintype "bidirectional"))
    )
    (net (code "96") (name "unconnected-(CONN1-PPT_GND-PadP$16)") (class "Default")
      (node (ref "CONN1") (pin "P$16") (pinfunction "PPT_GND_P$16") (pintype "bidirectional"))
    )
    (net (code "97") (name "unconnected-(CONN1-PPT_VBAT-PadP$2)") (class "Default")
      (node (ref "CONN1") (pin "P$2") (pinfunction "PPT_VBAT_P$2") (pintype "bidirectional"))
    )
    (net (code "98") (name "unconnected-(CONN1-PPT_VBAT-PadP$4)") (class "Default")
      (node (ref "CONN1") (pin "P$4") (pinfunction "PPT_VBAT_P$4") (pintype "bidirectional"))
    )
    (net (code "99") (name "unconnected-(CONN1-PPT_VBAT-PadP$5)") (class "Default")
      (node (ref "CONN1") (pin "P$5") (pinfunction "PPT_VBAT_P$5") (pintype "bidirectional"))
    )
    (net (code "100") (name "unconnected-(CONN1-PPT_VBAT-PadP$7)") (class "Default")
      (node (ref "CONN1") (pin "P$7") (pinfunction "PPT_VBAT_P$7") (pintype "bidirectional"))
    )
    (net (code "101") (name "unconnected-(CONN1-PPT_VBAT-PadP$10)") (class "Default")
      (node (ref "CONN1") (pin "P$10") (pinfunction "PPT_VBAT_P$10") (pintype "bidirectional"))
    )
    (net (code "102") (name "unconnected-(CONN1-PPT_VBAT-PadP$12)") (class "Default")
      (node (ref "CONN1") (pin "P$12") (pinfunction "PPT_VBAT_P$12") (pintype "bidirectional"))
    )
    (net (code "103") (name "unconnected-(CONN1-PPT_VBAT-PadP$13)") (class "Default")
      (node (ref "CONN1") (pin "P$13") (pinfunction "PPT_VBAT_P$13") (pintype "bidirectional"))
    )
    (net (code "104") (name "unconnected-(CONN1-PPT_VBAT-PadP$15)") (class "Default")
      (node (ref "CONN1") (pin "P$15") (pinfunction "PPT_VBAT_P$15") (pintype "bidirectional"))
    )
    (net (code "105") (name "unconnected-(CONN1-PadP$37)") (class "Default")
      (node (ref "CONN1") (pin "P$37") (pinfunction "P$37_P$37") (pintype "bidirectional"))
    )
    (net (code "106") (name "unconnected-(CONN1-PadP$38)") (class "Default")
      (node (ref "CONN1") (pin "P$38") (pinfunction "P$38_P$38") (pintype "bidirectional"))
    )
    (net (code "107") (name "unconnected-(CONN1-PadP$39)") (class "Default")
      (node (ref "CONN1") (pin "P$39") (pinfunction "P$39_P$39") (pintype "bidirectional"))
    )
    (net (code "108") (name "unconnected-(CONN1-PadP$40)") (class "Default")
      (node (ref "CONN1") (pin "P$40") (pinfunction "P$40_P$40") (pintype "bidirectional"))
    )
    (net (code "109") (name "unconnected-(CONN1-PadP$41)") (class "Default")
      (node (ref "CONN1") (pin "P$41") (pinfunction "P$41_P$41") (pintype "bidirectional"))
    )
    (net (code "110") (name "unconnected-(CONN1-PadP$42)") (class "Default")
      (node (ref "CONN1") (pin "P$42") (pinfunction "P$42_P$42") (pintype "bidirectional"))
    )
    (net (code "111") (name "unconnected-(CONN1-PadP$43)") (class "Default")
      (node (ref "CONN1") (pin "P$43") (pinfunction "P$43_P$43") (pintype "bidirectional"))
    )
    (net (code "112") (name "unconnected-(CONN1-PadP$44)") (class "Default")
      (node (ref "CONN1") (pin "P$44") (pinfunction "P$44_P$44") (pintype "bidirectional"))
    )
    (net (code "113") (name "unconnected-(CONN1-PadP$46)") (class "Default")
      (node (ref "CONN1") (pin "P$46") (pinfunction "P$46_P$46") (pintype "bidirectional"))
    )
    (net (code "114") (name "unconnected-(CONN1-PadP$47)") (class "Default")
      (node (ref "CONN1") (pin "P$47") (pinfunction "P$47_P$47") (pintype "bidirectional"))
    )
    (net (code "115") (name "unconnected-(CONN1-PadP$48)") (class "Default")
      (node (ref "CONN1") (pin "P$48") (pinfunction "P$48_P$48") (pintype "bidirectional"))
    )
    (net (code "116") (name "unconnected-(CONN1-PadP$50)") (class "Default")
      (node (ref "CONN1") (pin "P$50") (pinfunction "P$50_P$50") (pintype "bidirectional"))
    )
    (net (code "117") (name "unconnected-(CONN1-PadP$54)") (class "Default")
      (node (ref "CONN1") (pin "P$54") (pinfunction "P$54_P$54") (pintype "bidirectional"))
    )
    (net (code "118") (name "unconnected-(CONN1-PadP$58)") (class "Default")
      (node (ref "CONN1") (pin "P$58") (pinfunction "P$58_P$58") (pintype "bidirectional"))
    )
    (net (code "119") (name "unconnected-(CONN1-PadP$60)") (class "Default")
      (node (ref "CONN1") (pin "P$60") (pinfunction "P$60_P$60") (pintype "bidirectional"))
    )
    (net (code "120") (name "unconnected-(CONN1-PadP$61)") (class "Default")
      (node (ref "CONN1") (pin "P$61") (pinfunction "P$61_P$61") (pintype "bidirectional"))
    )
    (net (code "121") (name "unconnected-(CONN1-PadP$62)") (class "Default")
      (node (ref "CONN1") (pin "P$62") (pinfunction "P$62_P$62") (pintype "bidirectional"))
    )
    (net (code "122") (name "unconnected-(CONN1-PadP$63)") (class "Default")
      (node (ref "CONN1") (pin "P$63") (pinfunction "P$63_P$63") (pintype "bidirectional"))
    )
    (net (code "123") (name "unconnected-(CONN1-PadP$64)") (class "Default")
      (node (ref "CONN1") (pin "P$64") (pinfunction "P$64_P$64") (pintype "bidirectional"))
    )
    (net (code "124") (name "unconnected-(CONN1-PadP$65)") (class "Default")
      (node (ref "CONN1") (pin "P$65") (pinfunction "P$65_P$65") (pintype "bidirectional"))
    )
    (net (code "125") (name "unconnected-(CONN1-PadP$66)") (class "Default")
      (node (ref "CONN1") (pin "P$66") (pinfunction "P$66_P$66") (pintype "bidirectional"))
    )
    (net (code "126") (name "unconnected-(CONN1-PadP$67)") (class "Default")
      (node (ref "CONN1") (pin "P$67") (pinfunction "P$67_P$67") (pintype "bidirectional"))
    )
    (net (code "127") (name "unconnected-(CONN1-PadP$68)") (class "Default")
      (node (ref "CONN1") (pin "P$68") (pinfunction "P$68_P$68") (pintype "bidirectional"))
    )
    (net (code "128") (name "unconnected-(CONN1-PadP$73)") (class "Default")
      (node (ref "CONN1") (pin "P$73") (pinfunction "P$73_P$73") (pintype "bidirectional"))
    )
    (net (code "129") (name "unconnected-(CONN1-PadP$74)") (class "Default")
      (node (ref "CONN1") (pin "P$74") (pinfunction "P$74_P$74") (pintype "bidirectional"))
    )
    (net (code "130") (name "unconnected-(CONN1-PadP$75)") (class "Default")
      (node (ref "CONN1") (pin "P$75") (pinfunction "P$75_P$75") (pintype "bidirectional"))
    )
    (net (code "131") (name "unconnected-(CONN1-PadP$76)") (class "Default")
      (node (ref "CONN1") (pin "P$76") (pinfunction "P$76_P$76") (pintype "bidirectional"))
    )
    (net (code "132") (name "unconnected-(CONN1-PadP$81)") (class "Default")
      (node (ref "CONN1") (pin "P$81") (pinfunction "P$81_P$81") (pintype "bidirectional"))
    )
    (net (code "133") (name "unconnected-(CONN1-PadP$82)") (class "Default")
      (node (ref "CONN1") (pin "P$82") (pinfunction "P$82_P$82") (pintype "bidirectional"))
    )
    (net (code "134") (name "unconnected-(CONN1-PadP$83)") (class "Default")
      (node (ref "CONN1") (pin "P$83") (pinfunction "P$83_P$83") (pintype "bidirectional"))
    )
    (net (code "135") (name "unconnected-(CONN1-PadP$84)") (class "Default")
      (node (ref "CONN1") (pin "P$84") (pinfunction "P$84_P$84") (pintype "bidirectional"))
    )
    (net (code "136") (name "unconnected-(CONN1-PadP$89)") (class "Default")
      (node (ref "CONN1") (pin "P$89") (pinfunction "P$89_P$89") (pintype "bidirectional"))
    )
    (net (code "137") (name "unconnected-(CONN1-PadP$90)") (class "Default")
      (node (ref "CONN1") (pin "P$90") (pinfunction "P$90_P$90") (pintype "bidirectional"))
    )
    (net (code "138") (name "unconnected-(CONN1-PadP$91)") (class "Default")
      (node (ref "CONN1") (pin "P$91") (pinfunction "P$91_P$91") (pintype "bidirectional"))
    )
    (net (code "139") (name "unconnected-(CONN1-PadP$92)") (class "Default")
      (node (ref "CONN1") (pin "P$92") (pinfunction "P$92_P$92") (pintype "bidirectional"))
    )
    (net (code "140") (name "unconnected-(CONN1-PadP$95)") (class "Default")
      (node (ref "CONN1") (pin "P$95") (pinfunction "P$95_P$95") (pintype "bidirectional"))
    )
    (net (code "141") (name "unconnected-(CONN1-PadP$96)") (class "Default")
      (node (ref "CONN1") (pin "P$96") (pinfunction "P$96_P$96") (pintype "bidirectional"))
    )
    (net (code "142") (name "unconnected-(CONN1-RAHS_GND-PadP$94)") (class "Default")
      (node (ref "CONN1") (pin "P$94") (pinfunction "RAHS_GND_P$94") (pintype "bidirectional"))
    )
    (net (code "143") (name "unconnected-(CONN1-RAHS_VBAT-PadP$93)") (class "Default")
      (node (ref "CONN1") (pin "P$93") (pinfunction "RAHS_VBAT_P$93") (pintype "bidirectional"))
    )
    (net (code "144") (name "unconnected-(CONN1-TOPDEPLOY+-PadP$51)") (class "Default")
      (node (ref "CONN1") (pin "P$51") (pinfunction "TOPDEPLOY+_P$51") (pintype "bidirectional"))
    )
    (net (code "145") (name "unconnected-(CONN1-TOPDEPLOY+-PadP$55)") (class "Default")
      (node (ref "CONN1") (pin "P$55") (pinfunction "TOPDEPLOY+_P$55") (pintype "bidirectional"))
    )
    (net (code "146") (name "unconnected-(CONN1-TOPDEPLOY-$52-PadP$52)") (class "Default")
      (node (ref "CONN1") (pin "P$52") (pinfunction "TOPDEPLOY-$52_P$52") (pintype "bidirectional"))
    )
    (net (code "147") (name "unconnected-(CONN1-TOPDEPLOY-$56-PadP$56)") (class "Default")
      (node (ref "CONN1") (pin "P$56") (pinfunction "TOPDEPLOY-$56_P$56") (pintype "bidirectional"))
    )
    (net (code "148") (name "unconnected-(CONN1-WHEEL_GND-PadP$71)") (class "Default")
      (node (ref "CONN1") (pin "P$71") (pinfunction "WHEEL_GND_P$71") (pintype "bidirectional"))
    )
    (net (code "149") (name "unconnected-(CONN1-WHEEL_GND-PadP$72)") (class "Default")
      (node (ref "CONN1") (pin "P$72") (pinfunction "WHEEL_GND_P$72") (pintype "bidirectional"))
    )
    (net (code "150") (name "unconnected-(CONN1-WHEEL_VBAT-PadP$69)") (class "Default")
      (node (ref "CONN1") (pin "P$69") (pinfunction "WHEEL_VBAT_P$69") (pintype "bidirectional"))
    )
    (net (code "151") (name "unconnected-(CONN1-WHEEL_VBAT-PadP$70)") (class "Default")
      (node (ref "CONN1") (pin "P$70") (pinfunction "WHEEL_VBAT_P$70") (pintype "bidirectional"))
    )
    (net (code "152") (name "unconnected-(U3-EVENT1{slash}TXD3-PadP$9)") (class "Default")
      (node (ref "U3") (pin "P$9") (pinfunction "EVENT1/TXD3_P$9") (pintype "bidirectional"))
    )
    (net (code "153") (name "unconnected-(U3-EVENT2{slash}CAN1TX-PadP$7)") (class "Default")
      (node (ref "U3") (pin "P$7") (pinfunction "EVENT2/CAN1TX_P$7") (pintype "bidirectional"))
    )
    (net (code "154") (name "unconnected-(U3-NC-PadP$1)") (class "Default")
      (node (ref "U3") (pin "P$1") (pinfunction "NC_P$1") (pintype "bidirectional"))
    )
    (net (code "155") (name "unconnected-(U3-RXD1-PadP$12)") (class "Default")
      (node (ref "U3") (pin "P$12") (pinfunction "RXD1_P$12") (pintype "bidirectional"))
    )
    (net (code "156") (name "unconnected-(U3-TXD1-PadP$11)") (class "Default")
      (node (ref "U3") (pin "P$11") (pinfunction "TXD1_P$11") (pintype "bidirectional"))
    )
    (net (code "157") (name "unconnected-(U3-VARF{slash}CAN1RX-PadP$6)") (class "Default")
      (node (ref "U3") (pin "P$6") (pinfunction "VARF/CAN1RX_P$6") (pintype "bidirectional"))
    )
  )
)
